# Microcontroller.net
KiCad netlist of a schematic drawn in Altium Designer
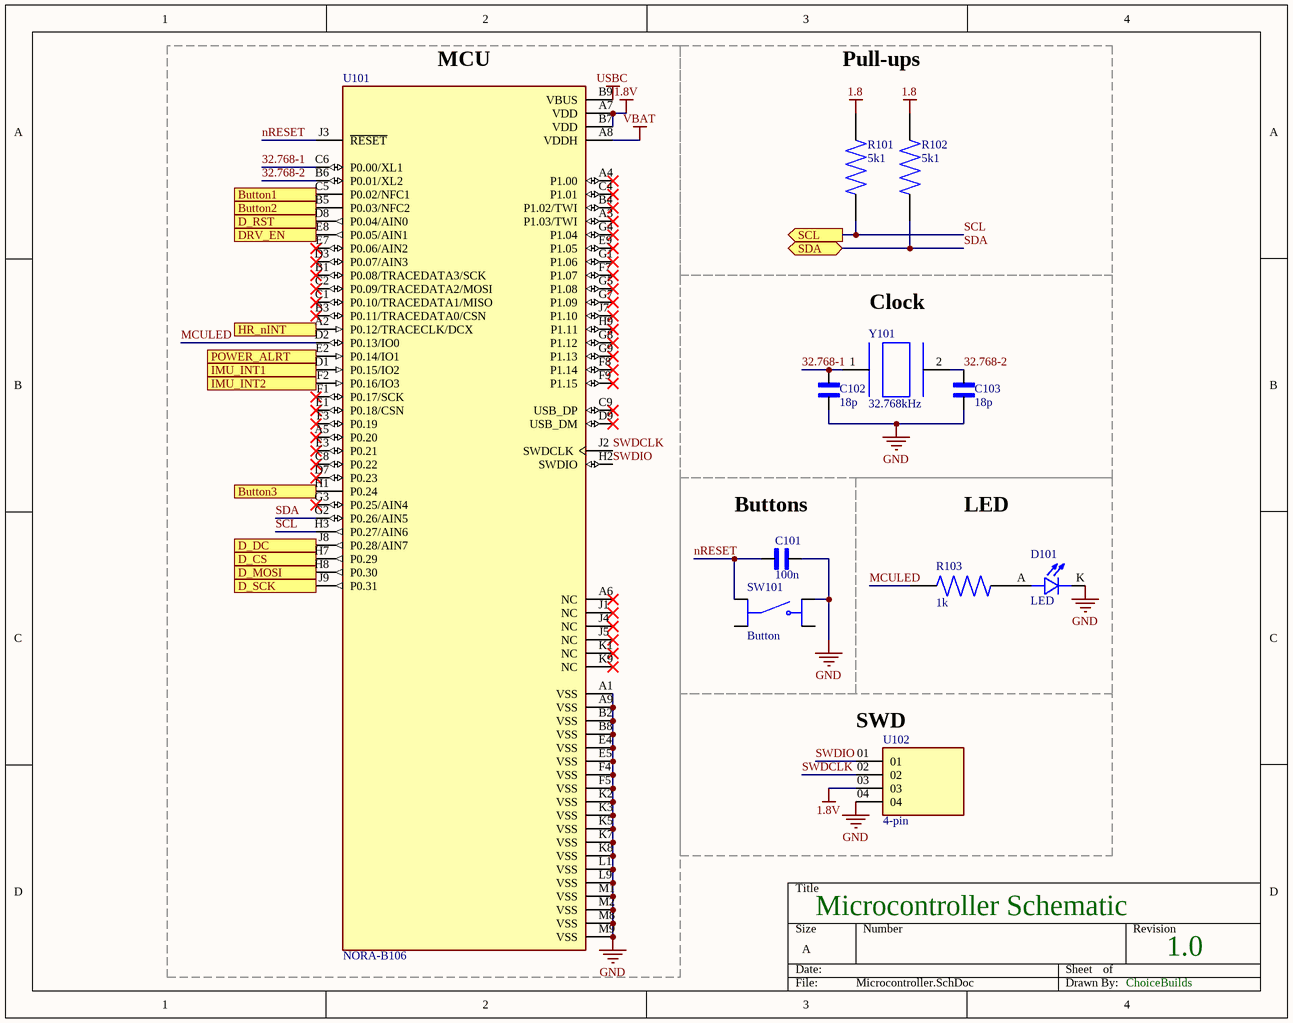
[diagram p0: Microcontroller.SchDoc]

(export (version "E")
  (design (tool "Eeschema 10.0.6"))
  (components
    (comp (ref "C101") (value "100n") (footprint "0402c") (libsource (lib "") (part "0402c_1")))
    (comp (ref "C102") (value "18p") (footprint "0402c") (libsource (lib "UbiWatch_SchLib") (part "0402c")))
    (comp (ref "C103") (value "18p") (footprint "0402c") (libsource (lib "UbiWatch_SchLib") (part "0402c")))
    (comp (ref "D101") (value "LED") (footprint ".LED") (libsource (lib "UbiWatch_SchLib") (part ".LED")))
    (comp (ref "R101") (value "5k1") (footprint "0402r") (libsource (lib "UbiWatch_SchLib") (part "0402r")))
    (comp (ref "R102") (value "5k1") (footprint "0402r") (libsource (lib "UbiWatch_SchLib") (part "0402r")))
    (comp (ref "R103") (value "1k") (footprint "0402r") (libsource (lib "UbiWatch_SchLib") (part "0402r")))
    (comp (ref "SW101")
      (value "Button")
      (footprint ".Button")
      (libsource (lib "UbiWatch_SchLib") (part ".Button"))
    )
    (comp (ref "U101")
      (value "NORA-B106")
      (footprint "NORA-B106")
      (libsource (lib "UbiWatch_SchLib") (part "NORA-B106"))
    )
    (comp (ref "U102") (value "4-pin") (footprint "4-pin") (libsource (lib "UbiWatch_SchLib") (part "4-pin")))
    (comp (ref "Y101")
      (value "32.768kHz")
      (footprint "32.768kHz")
      (libsource (lib "JWatch_SchLib") (part "32.768kHz"))
    )
  )
  (nets
    (net (code "1") (name "/32.768-1") (class "Default")
      (node (ref "C102") (pin "2") (pinfunction "2_2") (pintype "passive"))
      (node (ref "U101") (pin "C6") (pinfunction "P0.00/XL1_C6") (pintype "bidirectional"))
      (node (ref "Y101") (pin "1") (pinfunction "1_1") (pintype "passive"))
    )
    (net (code "2") (name "/32.768-2") (class "Default")
      (node (ref "C103") (pin "2") (pinfunction "2_2") (pintype "passive"))
      (node (ref "U101") (pin "B6") (pinfunction "P0.01/XL2_B6") (pintype "bidirectional"))
      (node (ref "Y101") (pin "2") (pinfunction "2_2") (pintype "passive"))
    )
    (net (code "3") (name "/Button1") (class "Default")
      (node (ref "U101") (pin "C5") (pinfunction "P0.02/NFC1_C5") (pintype "passive"))
    )
    (net (code "4") (name "/Button2") (class "Default")
      (node (ref "U101") (pin "B5") (pinfunction "P0.03/NFC2_B5") (pintype "passive"))
    )
    (net (code "5") (name "/Button3") (class "Default")
      (node (ref "U101") (pin "H1") (pinfunction "P0.24_H1") (pintype "passive"))
    )
    (net (code "6") (name "/DRV_EN") (class "Default")
      (node (ref "U101") (pin "E8") (pinfunction "P0.05/AIN1_E8") (pintype "output"))
    )
    (net (code "7") (name "/D_CS") (class "Default")
      (node (ref "U101") (pin "H7") (pinfunction "P0.29_H7") (pintype "output"))
    )
    (net (code "8") (name "/D_DC") (class "Default")
      (node (ref "U101") (pin "J8") (pinfunction "P0.28/AIN7_J8") (pintype "output"))
    )
    (net (code "9") (name "/D_MOSI") (class "Default")
      (node (ref "U101") (pin "H8") (pinfunction "P0.30_H8") (pintype "output"))
    )
    (net (code "10") (name "/D_RST") (class "Default")
      (node (ref "U101") (pin "D8") (pinfunction "P0.04/AIN0_D8") (pintype "output"))
    )
    (net (code "11") (name "/D_SCK") (class "Default")
      (node (ref "U101") (pin "J9") (pinfunction "P0.31_J9") (pintype "output"))
    )
    (net (code "12") (name "/HR_nINT") (class "Default")
      (node (ref "U101") (pin "A2") (pinfunction "P0.12/TRACECLK/DCX_A2") (pintype "input"))
    )
    (net (code "13") (name "/IMU_INT1") (class "Default")
      (node (ref "U101") (pin "D1") (pinfunction "P0.15/IO2_D1") (pintype "input"))
    )
    (net (code "14") (name "/IMU_INT2") (class "Default")
      (node (ref "U101") (pin "F2") (pinfunction "P0.16/IO3_F2") (pintype "input"))
    )
    (net (code "15") (name "/MCULED") (class "Default")
      (node (ref "R103") (pin "1") (pinfunction "1_1") (pintype "passive"))
      (node (ref "U101") (pin "D2") (pinfunction "P0.13/IO0_D2") (pintype "bidirectional"))
    )
    (net (code "16") (name "/POWER_ALRT") (class "Default")
      (node (ref "U101") (pin "E2") (pinfunction "P0.14/IO1_E2") (pintype "input"))
    )
    (net (code "17") (name "/SCL") (class "Default")
      (node (ref "R101") (pin "1") (pinfunction "1_1") (pintype "passive"))
      (node (ref "U101") (pin "H3") (pinfunction "P0.27/AIN6_H3") (pintype "output"))
    )
    (net (code "18") (name "/SDA") (class "Default")
      (node (ref "R102") (pin "1") (pinfunction "1_1") (pintype "passive"))
      (node (ref "U101") (pin "G2") (pinfunction "P0.26/AIN5_G2") (pintype "bidirectional"))
    )
    (net (code "19") (name "/SWDCLK") (class "Default")
      (node (ref "U101") (pin "J2") (pinfunction "SWDCLK_J2") (pintype "passive"))
      (node (ref "U102") (pin "02") (pinfunction "02_02") (pintype "passive"))
    )
    (net (code "20") (name "/SWDIO") (class "Default")
      (node (ref "U101") (pin "H2") (pinfunction "SWDIO_H2") (pintype "bidirectional"))
      (node (ref "U102") (pin "01") (pinfunction "01_01") (pintype "passive"))
    )
    (net (code "21") (name "/nRESET") (class "Default")
      (node (ref "C101") (pin "1") (pinfunction "1_1") (pintype "passive"))
      (node (ref "SW101") (pin "A1") (pinfunction "A1_A1") (pintype "passive"))
      (node (ref "U101") (pin "J3") (pinfunction "~{RESET}_J3") (pintype "passive"))
    )
    (net (code "22") (name "1.8") (class "Default")
      (node (ref "R101") (pin "2") (pinfunction "2_2") (pintype "passive"))
      (node (ref "R102") (pin "2") (pinfunction "2_2") (pintype "passive"))
    )
    (net (code "23") (name "1.8V") (class "Default")
      (node (ref "U101") (pin "A7") (pinfunction "VDD_A7") (pintype "power_in"))
      (node (ref "U101") (pin "B7") (pinfunction "VDD_B7") (pintype "power_in"))
      (node (ref "U102") (pin "03") (pinfunction "03_03") (pintype "passive"))
    )
    (net (code "24") (name "GND") (class "Default")
      (node (ref "C101") (pin "2") (pinfunction "2_2") (pintype "passive"))
      (node (ref "C102") (pin "1") (pinfunction "1_1") (pintype "passive"))
      (node (ref "C103") (pin "1") (pinfunction "1_1") (pintype "passive"))
      (node (ref "D101") (pin "K") (pinfunction "K_K") (pintype "passive"))
      (node (ref "SW101") (pin "B1") (pinfunction "B1_B1") (pintype "passive"))
      (node (ref "U101") (pin "A1") (pinfunction "VSS_A1") (pintype "power_in"))
      (node (ref "U101") (pin "A9") (pinfunction "VSS_A9") (pintype "power_in"))
      (node (ref "U101") (pin "B2") (pinfunction "VSS_B2") (pintype "power_in"))
      (node (ref "U101") (pin "B8") (pinfunction "VSS_B8") (pintype "power_in"))
      (node (ref "U101") (pin "E4") (pinfunction "VSS_E4") (pintype "power_in"))
      (node (ref "U101") (pin "E5") (pinfunction "VSS_E5") (pintype "power_in"))
      (node (ref "U101") (pin "F4") (pinfunction "VSS_F4") (pintype "power_in"))
      (node (ref "U101") (pin "F5") (pinfunction "VSS_F5") (pintype "power_in"))
      (node (ref "U101") (pin "K2") (pinfunction "VSS_K2") (pintype "power_in"))
      (node (ref "U101") (pin "K3") (pinfunction "VSS_K3") (pintype "power_in"))
      (node (ref "U101") (pin "K5") (pinfunction "VSS_K5") (pintype "power_in"))
      (node (ref "U101") (pin "K7") (pinfunction "VSS_K7") (pintype "power_in"))
      (node (ref "U101") (pin "K8") (pinfunction "VSS_K8") (pintype "power_in"))
      (node (ref "U101") (pin "L1") (pinfunction "VSS_L1") (pintype "power_in"))
      (node (ref "U101") (pin "L9") (pinfunction "VSS_L9") (pintype "power_in"))
      (node (ref "U101") (pin "M1") (pinfunction "VSS_M1") (pintype "power_in"))
      (node (ref "U101") (pin "M2") (pinfunction "VSS_M2") (pintype "power_in"))
      (node (ref "U101") (pin "M8") (pinfunction "VSS_M8") (pintype "power_in"))
      (node (ref "U101") (pin "M9") (pinfunction "VSS_M9") (pintype "power_in"))
      (node (ref "U102") (pin "04") (pinfunction "04_04") (pintype "passive"))
    )
    (net (code "25") (name "Net-(D101-PadA)") (class "Default")
      (node (ref "D101") (pin "A") (pinfunction "A_A") (pintype "passive"))
      (node (ref "R103") (pin "2") (pinfunction "2_2") (pintype "passive"))
    )
    (net (code "26") (name "USBC") (class "Default")
      (node (ref "U101") (pin "B9") (pinfunction "VBUS_B9") (pintype "power_in"))
    )
    (net (code "27") (name "VBAT") (class "Default")
      (node (ref "U101") (pin "A8") (pinfunction "VDDH_A8") (pintype "power_in"))
    )
    (net (code "28") (name "unconnected-(SW101-PadA2)") (class "Default")
      (node (ref "SW101") (pin "A2") (pinfunction "A2_A2") (pintype "passive"))
    )
    (net (code "29") (name "unconnected-(SW101-PadB2)") (class "Default")
      (node (ref "SW101") (pin "B2") (pinfunction "B2_B2") (pintype "passive"))
    )
    (net (code "30") (name "unconnected-(U101-NC-PadA6)") (class "Default")
      (node (ref "U101") (pin "A6") (pinfunction "NC_A6") (pintype "passive+no_connect"))
    )
    (net (code "31") (name "unconnected-(U101-NC-PadJ1)") (class "Default")
      (node (ref "U101") (pin "J1") (pinfunction "NC_J1") (pintype "passive+no_connect"))
    )
    (net (code "32") (name "unconnected-(U101-NC-PadJ4)") (class "Default")
      (node (ref "U101") (pin "J4") (pinfunction "NC_J4") (pintype "passive+no_connect"))
    )
    (net (code "33") (name "unconnected-(U101-NC-PadJ5)") (class "Default")
      (node (ref "U101") (pin "J5") (pinfunction "NC_J5") (pintype "passive+no_connect"))
    )
    (net (code "34") (name "unconnected-(U101-NC-PadK1)") (class "Default")
      (node (ref "U101") (pin "K1") (pinfunction "NC_K1") (pintype "passive+no_connect"))
    )
    (net (code "35") (name "unconnected-(U101-NC-PadK9)") (class "Default")
      (node (ref "U101") (pin "K9") (pinfunction "NC_K9") (pintype "passive+no_connect"))
    )
    (net (code "36") (name "unconnected-(U101-P0.06{slash}AIN2-PadE7)") (class "Default")
      (node (ref "U101") (pin "E7") (pinfunction "P0.06/AIN2_E7") (pintype "bidirectional+no_connect"))
    )
    (net (code "37") (name "unconnected-(U101-P0.07{slash}AIN3-PadD3)") (class "Default")
      (node (ref "U101") (pin "D3") (pinfunction "P0.07/AIN3_D3") (pintype "bidirectional+no_connect"))
    )
    (net (code "38") (name "unconnected-(U101-P0.08{slash}TRACEDATA3{slash}SCK-PadB1)") (class "Default")
      (node (ref "U101") (pin "B1") (pinfunction "P0.08/TRACEDATA3/SCK_B1") (pintype "bidirectional+no_connect"))
    )
    (net (code "39") (name "unconnected-(U101-P0.09{slash}TRACEDATA2{slash}MOSI-PadC2)") (class "Default")
      (node (ref "U101") (pin "C2") (pinfunction "P0.09/TRACEDATA2/MOSI_C2") (pintype "bidirectional+no_connect"))
    )
    (net (code "40") (name "unconnected-(U101-P0.10{slash}TRACEDATA1{slash}MISO-PadC1)") (class "Default")
      (node (ref "U101") (pin "C1") (pinfunction "P0.10/TRACEDATA1/MISO_C1") (pintype "bidirectional+no_connect"))
    )
    (net (code "41") (name "unconnected-(U101-P0.11{slash}TRACEDATA0{slash}CSN-PadB3)") (class "Default")
      (node (ref "U101") (pin "B3") (pinfunction "P0.11/TRACEDATA0/CSN_B3") (pintype "bidirectional+no_connect"))
    )
    (net (code "42") (name "unconnected-(U101-P0.17{slash}SCK-PadF1)") (class "Default")
      (node (ref "U101") (pin "F1") (pinfunction "P0.17/SCK_F1") (pintype "bidirectional+no_connect"))
    )
    (net (code "43") (name "unconnected-(U101-P0.18{slash}CSN-PadE1)") (class "Default")
      (node (ref "U101") (pin "E1") (pinfunction "P0.18/CSN_E1") (pintype "bidirectional+no_connect"))
    )
    (net (code "44") (name "unconnected-(U101-P0.19-PadF3)") (class "Default")
      (node (ref "U101") (pin "F3") (pinfunction "P0.19_F3") (pintype "bidirectional+no_connect"))
    )
    (net (code "45") (name "unconnected-(U101-P0.20-PadA5)") (class "Default")
      (node (ref "U101") (pin "A5") (pinfunction "P0.20_A5") (pintype "bidirectional+no_connect"))
    )
    (net (code "46") (name "unconnected-(U101-P0.21-PadE3)") (class "Default")
      (node (ref "U101") (pin "E3") (pinfunction "P0.21_E3") (pintype "bidirectional+no_connect"))
    )
    (net (code "47") (name "unconnected-(U101-P0.22-PadC8)") (class "Default")
      (node (ref "U101") (pin "C8") (pinfunction "P0.22_C8") (pintype "bidirectional+no_connect"))
    )
    (net (code "48") (name "unconnected-(U101-P0.23-PadD7)") (class "Default")
      (node (ref "U101") (pin "D7") (pinfunction "P0.23_D7") (pintype "bidirectional+no_connect"))
    )
    (net (code "49") (name "unconnected-(U101-P0.25{slash}AIN4-PadG3)") (class "Default")
      (node (ref "U101") (pin "G3") (pinfunction "P0.25/AIN4_G3") (pintype "bidirectional+no_connect"))
    )
    (net (code "50") (name "unconnected-(U101-P1.00-PadA4)") (class "Default")
      (node (ref "U101") (pin "A4") (pinfunction "P1.00_A4") (pintype "bidirectional+no_connect"))
    )
    (net (code "51") (name "unconnected-(U101-P1.01-PadC4)") (class "Default")
      (node (ref "U101") (pin "C4") (pinfunction "P1.01_C4") (pintype "bidirectional+no_connect"))
    )
    (net (code "52") (name "unconnected-(U101-P1.02{slash}TWI-PadB4)") (class "Default")
      (node (ref "U101") (pin "B4") (pinfunction "P1.02/TWI_B4") (pintype "bidirectional+no_connect"))
    )
    (net (code "53") (name "unconnected-(U101-P1.03{slash}TWI-PadA3)") (class "Default")
      (node (ref "U101") (pin "A3") (pinfunction "P1.03/TWI_A3") (pintype "bidirectional+no_connect"))
    )
    (net (code "54") (name "unconnected-(U101-P1.04-PadG4)") (class "Default")
      (node (ref "U101") (pin "G4") (pinfunction "P1.04_G4") (pintype "bidirectional+no_connect"))
    )
    (net (code "55") (name "unconnected-(U101-P1.05-PadE9)") (class "Default")
      (node (ref "U101") (pin "E9") (pinfunction "P1.05_E9") (pintype "bidirectional+no_connect"))
    )
    (net (code "56") (name "unconnected-(U101-P1.06-PadG1)") (class "Default")
      (node (ref "U101") (pin "G1") (pinfunction "P1.06_G1") (pintype "bidirectional+no_connect"))
    )
    (net (code "57") (name "unconnected-(U101-P1.07-PadF7)") (class "Default")
      (node (ref "U101") (pin "F7") (pinfunction "P1.07_F7") (pintype "bidirectional+no_connect"))
    )
    (net (code "58") (name "unconnected-(U101-P1.08-PadG5)") (class "Default")
      (node (ref "U101") (pin "G5") (pinfunction "P1.08_G5") (pintype "bidirectional+no_connect"))
    )
    (net (code "59") (name "unconnected-(U101-P1.09-PadG7)") (class "Default")
      (node (ref "U101") (pin "G7") (pinfunction "P1.09_G7") (pintype "bidirectional+no_connect"))
    )
    (net (code "60") (name "unconnected-(U101-P1.10-PadJ7)") (class "Default")
      (node (ref "U101") (pin "J7") (pinfunction "P1.10_J7") (pintype "bidirectional+no_connect"))
    )
    (net (code "61") (name "unconnected-(U101-P1.11-PadH9)") (class "Default")
      (node (ref "U101") (pin "H9") (pinfunction "P1.11_H9") (pintype "bidirectional+no_connect"))
    )
    (net (code "62") (name "unconnected-(U101-P1.12-PadG8)") (class "Default")
      (node (ref "U101") (pin "G8") (pinfunction "P1.12_G8") (pintype "bidirectional+no_connect"))
    )
    (net (code "63") (name "unconnected-(U101-P1.13-PadG9)") (class "Default")
      (node (ref "U101") (pin "G9") (pinfunction "P1.13_G9") (pintype "bidirectional+no_connect"))
    )
    (net (code "64") (name "unconnected-(U101-P1.14-PadF8)") (class "Default")
      (node (ref "U101") (pin "F8") (pinfunction "P1.14_F8") (pintype "bidirectional+no_connect"))
    )
    (net (code "65") (name "unconnected-(U101-P1.15-PadF9)") (class "Default")
      (node (ref "U101") (pin "F9") (pinfunction "P1.15_F9") (pintype "bidirectional+no_connect"))
    )
    (net (code "66") (name "unconnected-(U101-USB_DM-PadD9)") (class "Default")
      (node (ref "U101") (pin "D9") (pinfunction "USB_DM_D9") (pintype "bidirectional+no_connect"))
    )
    (net (code "67") (name "unconnected-(U101-USB_DP-PadC9)") (class "Default")
      (node (ref "U101") (pin "C9") (pinfunction "USB_DP_C9") (pintype "bidirectional+no_connect"))
    )
  )
)
